# BPMLabLineTX.net
KiCad netlist of a schematic drawn in EAGLE
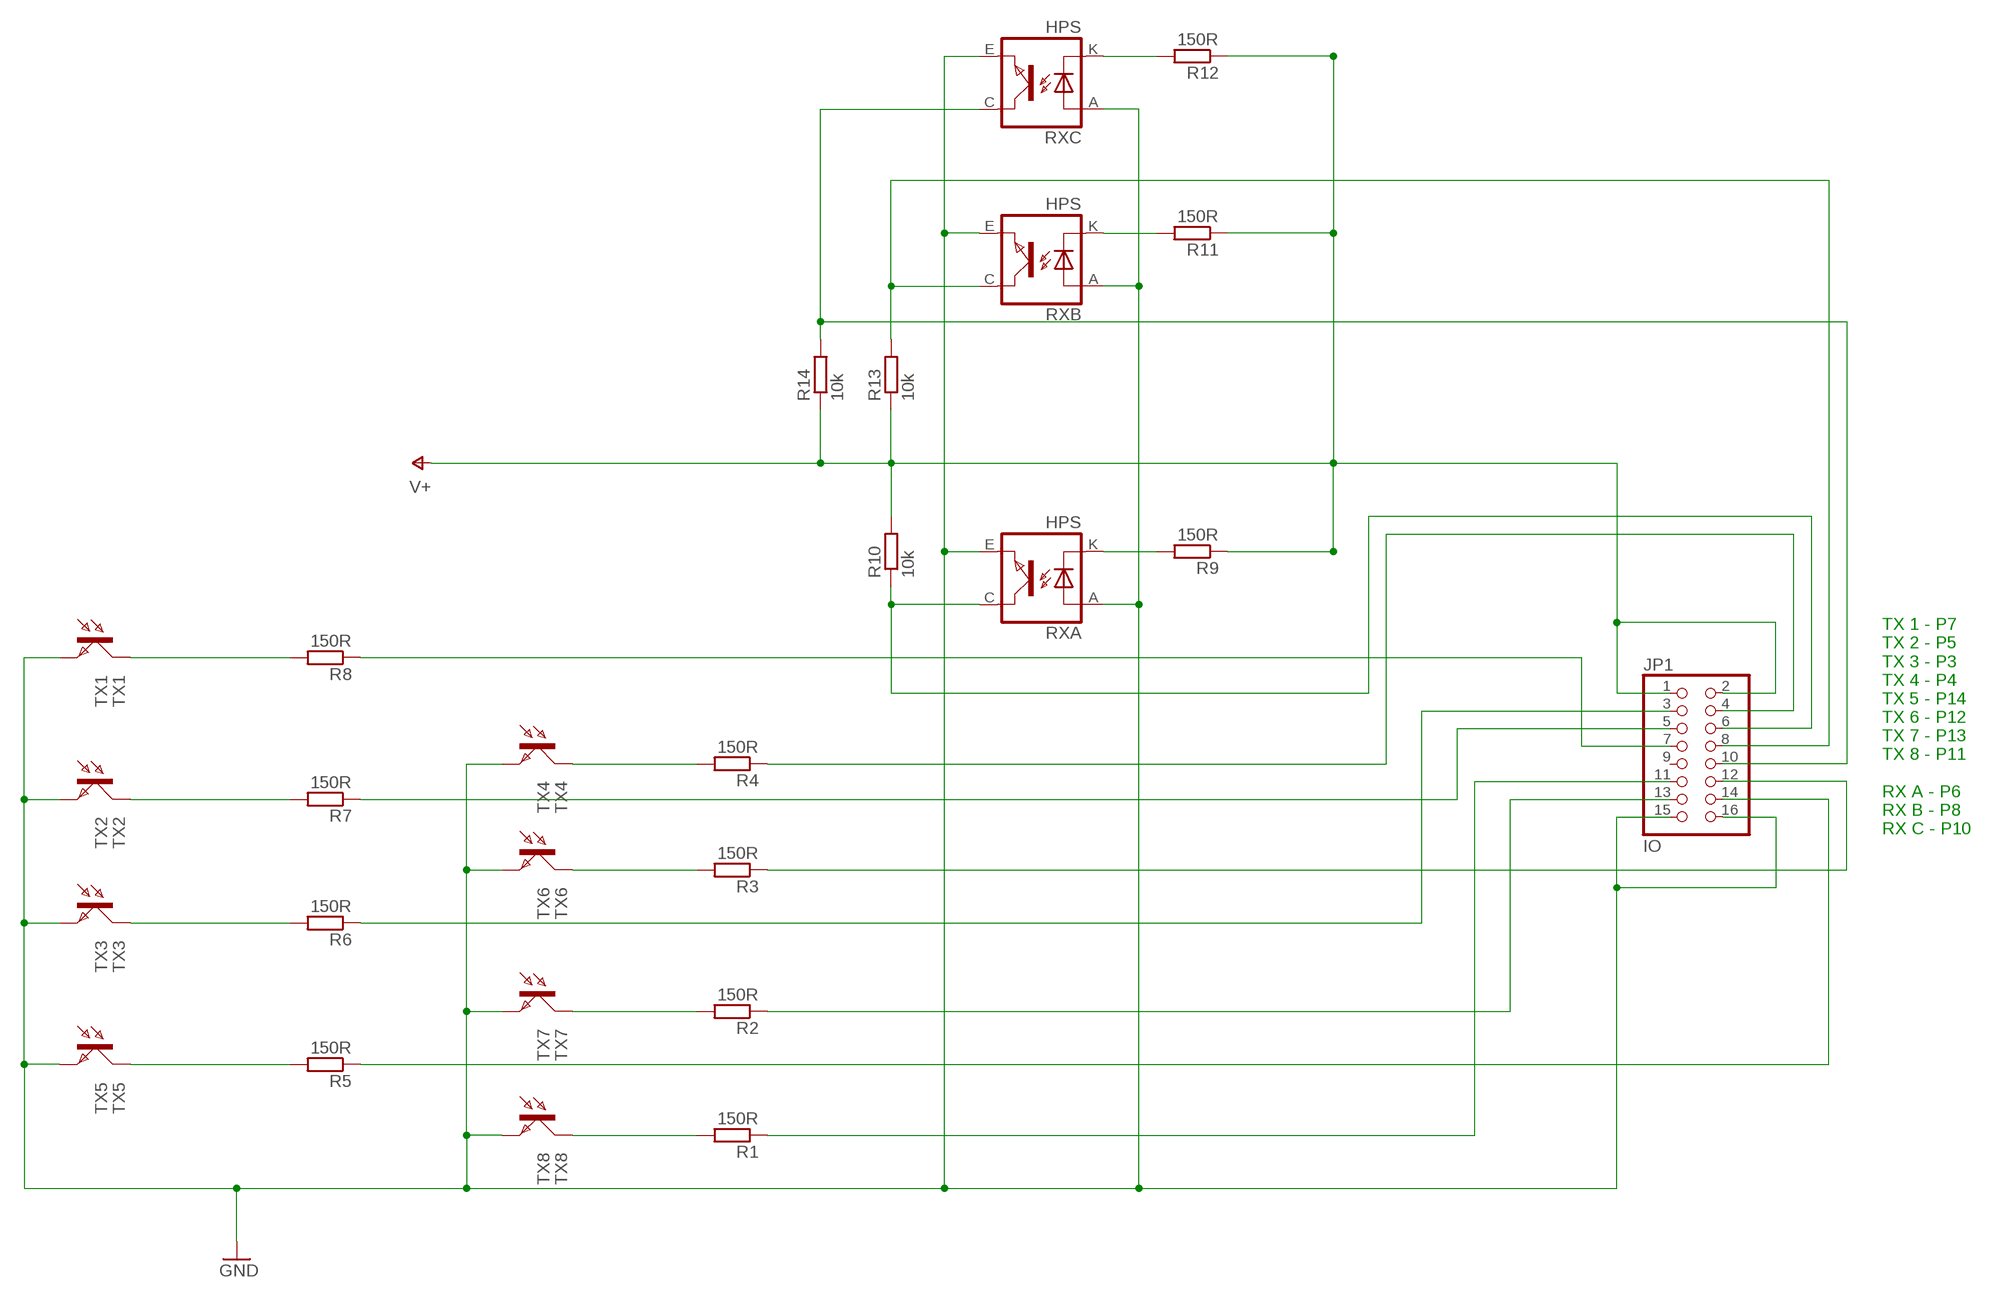
[diagram p0: schematic, sheet 1]

(export (version "E")
  (design (tool "Eeschema 10.0.6"))
  (components
    (comp (ref "JP1")
      (value "IO")
      (footprint "eagle-import:2X08")
      (libsource (lib "eagle-import") (part "PINHD-2X8"))
    )
    (comp (ref "R1")
      (value "150R")
      (footprint "eagle-import:M0805")
      (libsource (lib "eagle-import") (part "R-EU_M0805"))
    )
    (comp (ref "R2")
      (value "150R")
      (footprint "eagle-import:M0805")
      (libsource (lib "eagle-import") (part "R-EU_M0805"))
    )
    (comp (ref "R3")
      (value "150R")
      (footprint "eagle-import:M0805")
      (libsource (lib "eagle-import") (part "R-EU_M0805"))
    )
    (comp (ref "R4")
      (value "150R")
      (footprint "eagle-import:M0805")
      (libsource (lib "eagle-import") (part "R-EU_M0805"))
    )
    (comp (ref "R5")
      (value "150R")
      (footprint "eagle-import:M0805")
      (libsource (lib "eagle-import") (part "R-EU_M0805"))
    )
    (comp (ref "R6")
      (value "150R")
      (footprint "eagle-import:M0805")
      (libsource (lib "eagle-import") (part "R-EU_M0805"))
    )
    (comp (ref "R7")
      (value "150R")
      (footprint "eagle-import:M0805")
      (libsource (lib "eagle-import") (part "R-EU_M0805"))
    )
    (comp (ref "R8")
      (value "150R")
      (footprint "eagle-import:M0805")
      (libsource (lib "eagle-import") (part "R-EU_M0805"))
    )
    (comp (ref "R9")
      (value "150R")
      (footprint "eagle-import:M0805")
      (libsource (lib "eagle-import") (part "R-EU_M0805"))
    )
    (comp (ref "R10")
      (value "10k")
      (footprint "eagle-import:M0805")
      (libsource (lib "eagle-import") (part "R-EU_M0805"))
    )
    (comp (ref "R11")
      (value "150R")
      (footprint "eagle-import:M0805")
      (libsource (lib "eagle-import") (part "R-EU_M0805"))
    )
    (comp (ref "R12")
      (value "150R")
      (footprint "eagle-import:M0805")
      (libsource (lib "eagle-import") (part "R-EU_M0805"))
    )
    (comp (ref "R13")
      (value "10k")
      (footprint "eagle-import:M0805")
      (libsource (lib "eagle-import") (part "R-EU_M0805"))
    )
    (comp (ref "R14")
      (value "10k")
      (footprint "eagle-import:M0805")
      (libsource (lib "eagle-import") (part "R-EU_M0805"))
    )
    (comp (ref "RXA")
      (value "HPS")
      (footprint "eagle-import:TCRT5000")
      (libsource (lib "eagle-import") (part "TCRT5000"))
    )
    (comp (ref "RXB")
      (value "HPS")
      (footprint "eagle-import:TCRT5000")
      (libsource (lib "eagle-import") (part "TCRT5000"))
    )
    (comp (ref "RXC")
      (value "HPS")
      (footprint "eagle-import:TCRT5000")
      (libsource (lib "eagle-import") (part "TCRT5000"))
    )
    (comp (ref "TX1")
      (value "TX1")
      (footprint "eagle-import:BPX81")
      (libsource (lib "eagle-import") (part "BPX81"))
    )
    (comp (ref "TX2")
      (value "TX2")
      (footprint "eagle-import:BPX81")
      (libsource (lib "eagle-import") (part "BPX81"))
    )
    (comp (ref "TX3")
      (value "TX3")
      (footprint "eagle-import:BPX81")
      (libsource (lib "eagle-import") (part "BPX81"))
    )
    (comp (ref "TX4")
      (value "TX4")
      (footprint "eagle-import:BPX81")
      (libsource (lib "eagle-import") (part "BPX81"))
    )
    (comp (ref "TX5")
      (value "TX5")
      (footprint "eagle-import:BPX81")
      (libsource (lib "eagle-import") (part "BPX81"))
    )
    (comp (ref "TX6")
      (value "TX6")
      (footprint "eagle-import:BPX81")
      (libsource (lib "eagle-import") (part "BPX81"))
    )
    (comp (ref "TX7")
      (value "TX7")
      (footprint "eagle-import:BPX81")
      (libsource (lib "eagle-import") (part "BPX81"))
    )
    (comp (ref "TX8")
      (value "TX8")
      (footprint "eagle-import:BPX81")
      (libsource (lib "eagle-import") (part "BPX81"))
    )
  )
  (nets
    (net (code "1") (name "GND") (class "Default")
      (node (ref "JP1") (pin "15") (pinfunction "15_15") (pintype "passive"))
      (node (ref "JP1") (pin "16") (pinfunction "16_16") (pintype "passive"))
      (node (ref "RXA") (pin "A") (pinfunction "ANODE_A") (pintype "passive"))
      (node (ref "RXA") (pin "E") (pinfunction "EMITTER_E") (pintype "passive"))
      (node (ref "RXB") (pin "A") (pinfunction "ANODE_A") (pintype "passive"))
      (node (ref "RXB") (pin "E") (pinfunction "EMITTER_E") (pintype "passive"))
      (node (ref "RXC") (pin "A") (pinfunction "ANODE_A") (pintype "passive"))
      (node (ref "RXC") (pin "E") (pinfunction "EMITTER_E") (pintype "passive"))
      (node (ref "TX1") (pin "E") (pinfunction "E_E") (pintype "passive"))
      (node (ref "TX2") (pin "E") (pinfunction "E_E") (pintype "passive"))
      (node (ref "TX3") (pin "E") (pinfunction "E_E") (pintype "passive"))
      (node (ref "TX4") (pin "E") (pinfunction "E_E") (pintype "passive"))
      (node (ref "TX5") (pin "E") (pinfunction "E_E") (pintype "passive"))
      (node (ref "TX6") (pin "E") (pinfunction "E_E") (pintype "passive"))
      (node (ref "TX7") (pin "E") (pinfunction "E_E") (pintype "passive"))
      (node (ref "TX8") (pin "E") (pinfunction "E_E") (pintype "passive"))
    )
    (net (code "2") (name "Net-(JP1-Pad3)") (class "Default")
      (node (ref "JP1") (pin "3") (pinfunction "3_3") (pintype "passive"))
      (node (ref "R6") (pin "1") (pinfunction "1_1") (pintype "passive"))
    )
    (net (code "3") (name "Net-(JP1-Pad4)") (class "Default")
      (node (ref "JP1") (pin "4") (pinfunction "4_4") (pintype "passive"))
      (node (ref "R4") (pin "1") (pinfunction "1_1") (pintype "passive"))
    )
    (net (code "4") (name "Net-(JP1-Pad5)") (class "Default")
      (node (ref "JP1") (pin "5") (pinfunction "5_5") (pintype "passive"))
      (node (ref "R7") (pin "1") (pinfunction "1_1") (pintype "passive"))
    )
    (net (code "5") (name "Net-(JP1-Pad7)") (class "Default")
      (node (ref "JP1") (pin "7") (pinfunction "7_7") (pintype "passive"))
      (node (ref "R8") (pin "1") (pinfunction "1_1") (pintype "passive"))
    )
    (net (code "6") (name "Net-(JP1-Pad11)") (class "Default")
      (node (ref "JP1") (pin "11") (pinfunction "11_11") (pintype "passive"))
      (node (ref "R1") (pin "1") (pinfunction "1_1") (pintype "passive"))
    )
    (net (code "7") (name "Net-(JP1-Pad12)") (class "Default")
      (node (ref "JP1") (pin "12") (pinfunction "12_12") (pintype "passive"))
      (node (ref "R3") (pin "1") (pinfunction "1_1") (pintype "passive"))
    )
    (net (code "8") (name "Net-(JP1-Pad13)") (class "Default")
      (node (ref "JP1") (pin "13") (pinfunction "13_13") (pintype "passive"))
      (node (ref "R2") (pin "1") (pinfunction "1_1") (pintype "passive"))
    )
    (net (code "9") (name "Net-(JP1-Pad14)") (class "Default")
      (node (ref "JP1") (pin "14") (pinfunction "14_14") (pintype "passive"))
      (node (ref "R5") (pin "1") (pinfunction "1_1") (pintype "passive"))
    )
    (net (code "10") (name "Net-(R1-Pad2)") (class "Default")
      (node (ref "R1") (pin "2") (pinfunction "2_2") (pintype "passive"))
      (node (ref "TX8") (pin "C") (pinfunction "C_C") (pintype "passive"))
    )
    (net (code "11") (name "Net-(R2-Pad2)") (class "Default")
      (node (ref "R2") (pin "2") (pinfunction "2_2") (pintype "passive"))
      (node (ref "TX7") (pin "C") (pinfunction "C_C") (pintype "passive"))
    )
    (net (code "12") (name "Net-(R3-Pad2)") (class "Default")
      (node (ref "R3") (pin "2") (pinfunction "2_2") (pintype "passive"))
      (node (ref "TX6") (pin "C") (pinfunction "C_C") (pintype "passive"))
    )
    (net (code "13") (name "Net-(R4-Pad2)") (class "Default")
      (node (ref "R4") (pin "2") (pinfunction "2_2") (pintype "passive"))
      (node (ref "TX4") (pin "C") (pinfunction "C_C") (pintype "passive"))
    )
    (net (code "14") (name "Net-(R5-Pad2)") (class "Default")
      (node (ref "R5") (pin "2") (pinfunction "2_2") (pintype "passive"))
      (node (ref "TX5") (pin "C") (pinfunction "C_C") (pintype "passive"))
    )
    (net (code "15") (name "Net-(R6-Pad2)") (class "Default")
      (node (ref "R6") (pin "2") (pinfunction "2_2") (pintype "passive"))
      (node (ref "TX3") (pin "C") (pinfunction "C_C") (pintype "passive"))
    )
    (net (code "16") (name "Net-(R7-Pad2)") (class "Default")
      (node (ref "R7") (pin "2") (pinfunction "2_2") (pintype "passive"))
      (node (ref "TX2") (pin "C") (pinfunction "C_C") (pintype "passive"))
    )
    (net (code "17") (name "Net-(R8-Pad2)") (class "Default")
      (node (ref "R8") (pin "2") (pinfunction "2_2") (pintype "passive"))
      (node (ref "TX1") (pin "C") (pinfunction "C_C") (pintype "passive"))
    )
    (net (code "18") (name "Net-(RXA-CATHODE)") (class "Default")
      (node (ref "R9") (pin "2") (pinfunction "2_2") (pintype "passive"))
      (node (ref "RXA") (pin "K") (pinfunction "CATHODE_K") (pintype "passive"))
    )
    (net (code "19") (name "Net-(RXA-COLLECTOR)") (class "Default")
      (node (ref "JP1") (pin "6") (pinfunction "6_6") (pintype "passive"))
      (node (ref "R10") (pin "1") (pinfunction "1_1") (pintype "passive"))
      (node (ref "RXA") (pin "C") (pinfunction "COLLECTOR_C") (pintype "passive"))
    )
    (net (code "20") (name "Net-(RXB-CATHODE)") (class "Default")
      (node (ref "R11") (pin "2") (pinfunction "2_2") (pintype "passive"))
      (node (ref "RXB") (pin "K") (pinfunction "CATHODE_K") (pintype "passive"))
    )
    (net (code "21") (name "Net-(RXB-COLLECTOR)") (class "Default")
      (node (ref "JP1") (pin "8") (pinfunction "8_8") (pintype "passive"))
      (node (ref "R13") (pin "2") (pinfunction "2_2") (pintype "passive"))
      (node (ref "RXB") (pin "C") (pinfunction "COLLECTOR_C") (pintype "passive"))
    )
    (net (code "22") (name "Net-(RXC-CATHODE)") (class "Default")
      (node (ref "R12") (pin "2") (pinfunction "2_2") (pintype "passive"))
      (node (ref "RXC") (pin "K") (pinfunction "CATHODE_K") (pintype "passive"))
    )
    (net (code "23") (name "Net-(RXC-COLLECTOR)") (class "Default")
      (node (ref "JP1") (pin "10") (pinfunction "10_10") (pintype "passive"))
      (node (ref "R14") (pin "2") (pinfunction "2_2") (pintype "passive"))
      (node (ref "RXC") (pin "C") (pinfunction "COLLECTOR_C") (pintype "passive"))
    )
    (net (code "24") (name "V+") (class "Default")
      (node (ref "JP1") (pin "1") (pinfunction "1_1") (pintype "passive"))
      (node (ref "JP1") (pin "2") (pinfunction "2_2") (pintype "passive"))
      (node (ref "R10") (pin "2") (pinfunction "2_2") (pintype "passive"))
      (node (ref "R11") (pin "1") (pinfunction "1_1") (pintype "passive"))
      (node (ref "R12") (pin "1") (pinfunction "1_1") (pintype "passive"))
      (node (ref "R13") (pin "1") (pinfunction "1_1") (pintype "passive"))
      (node (ref "R14") (pin "1") (pinfunction "1_1") (pintype "passive"))
      (node (ref "R9") (pin "1") (pinfunction "1_1") (pintype "passive"))
    )
    (net (code "25") (name "unconnected-(JP1-Pad9)") (class "Default")
      (node (ref "JP1") (pin "9") (pinfunction "9_9") (pintype "passive"))
    )
  )
)
